# Server_CPU_IO.net
KiCad netlist of a schematic drawn in Altium Designer
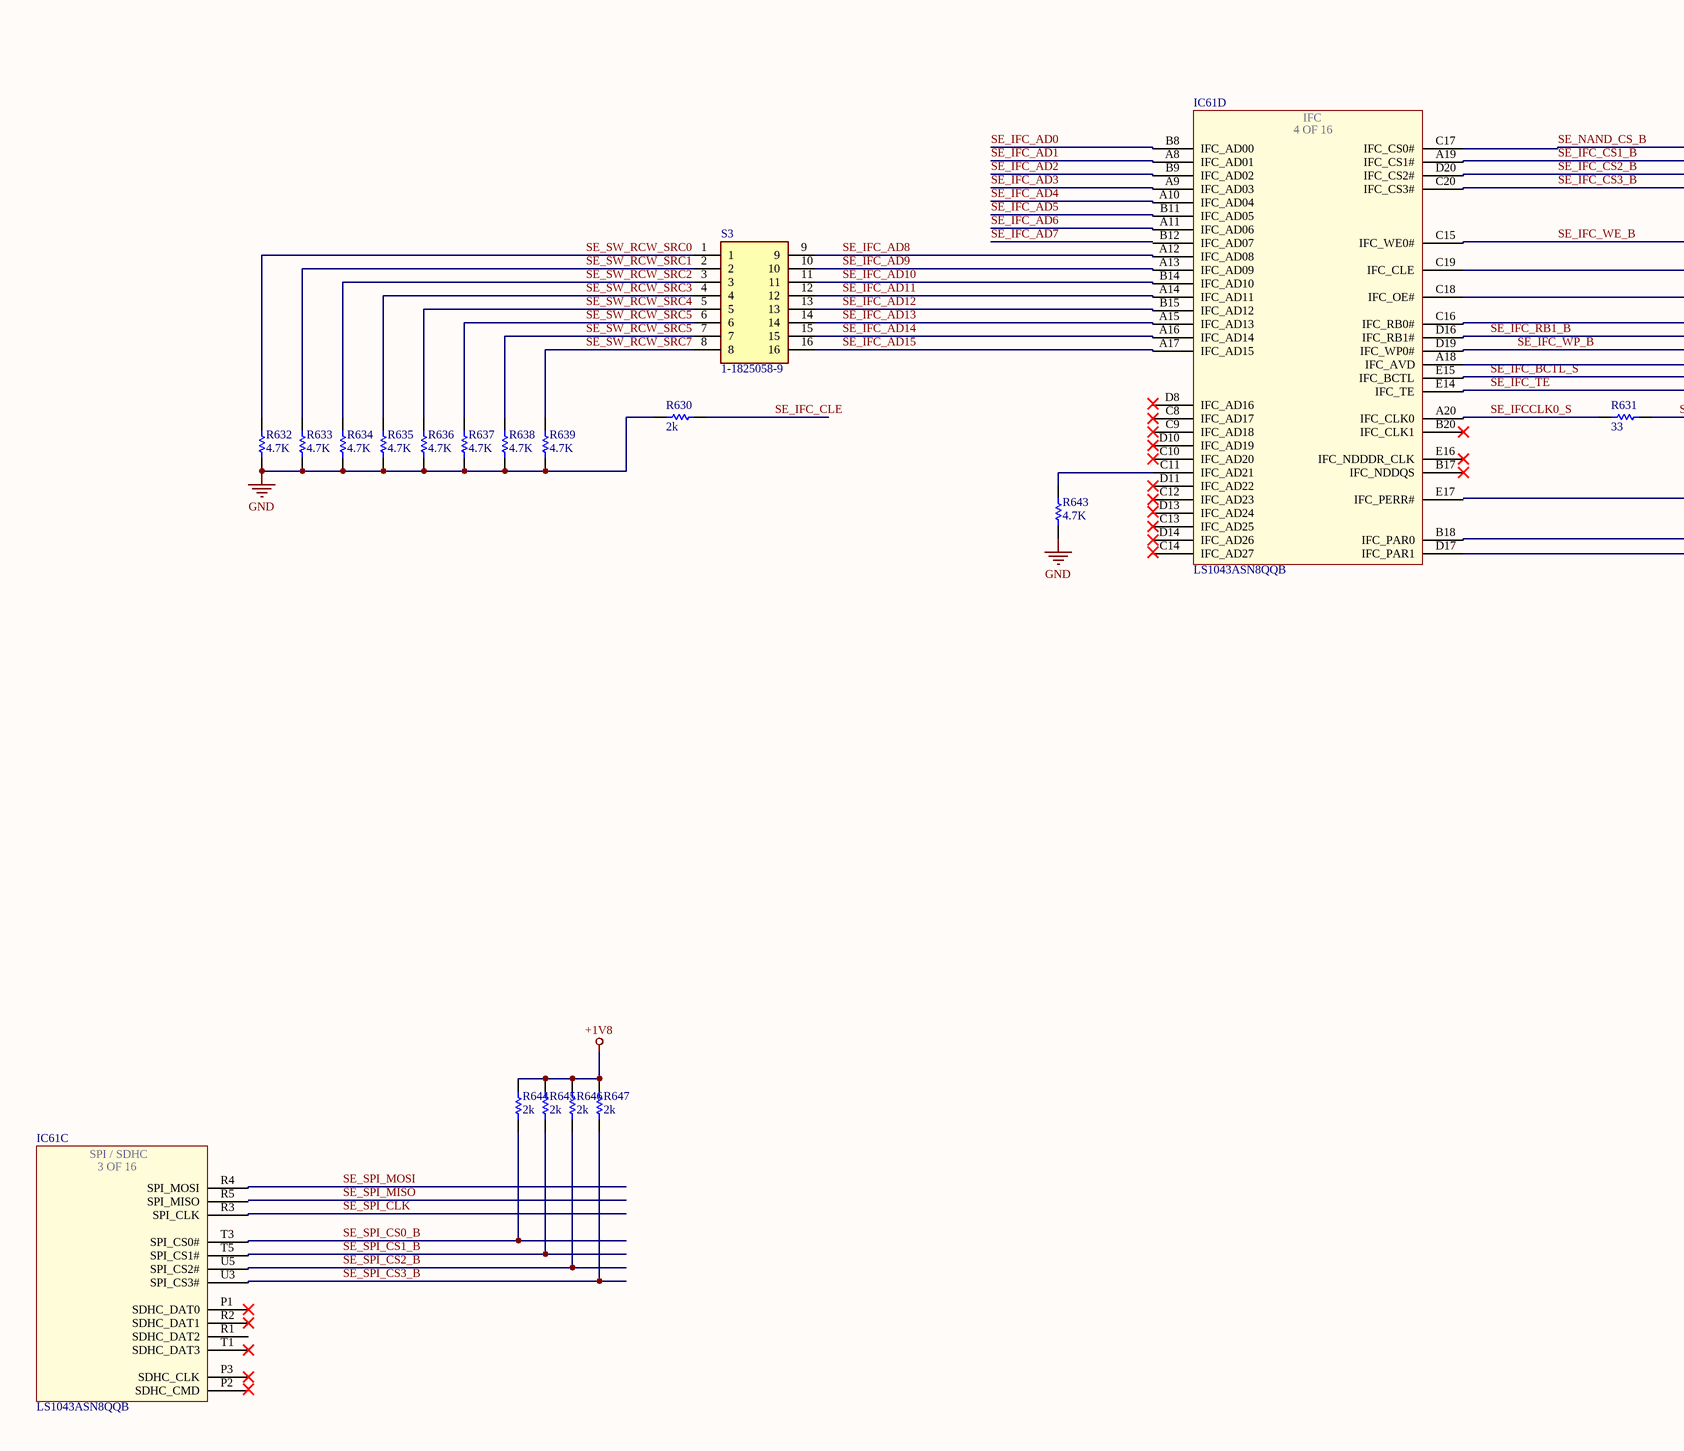
[diagram p0: Server_CPU_IO.SchDoc, left]
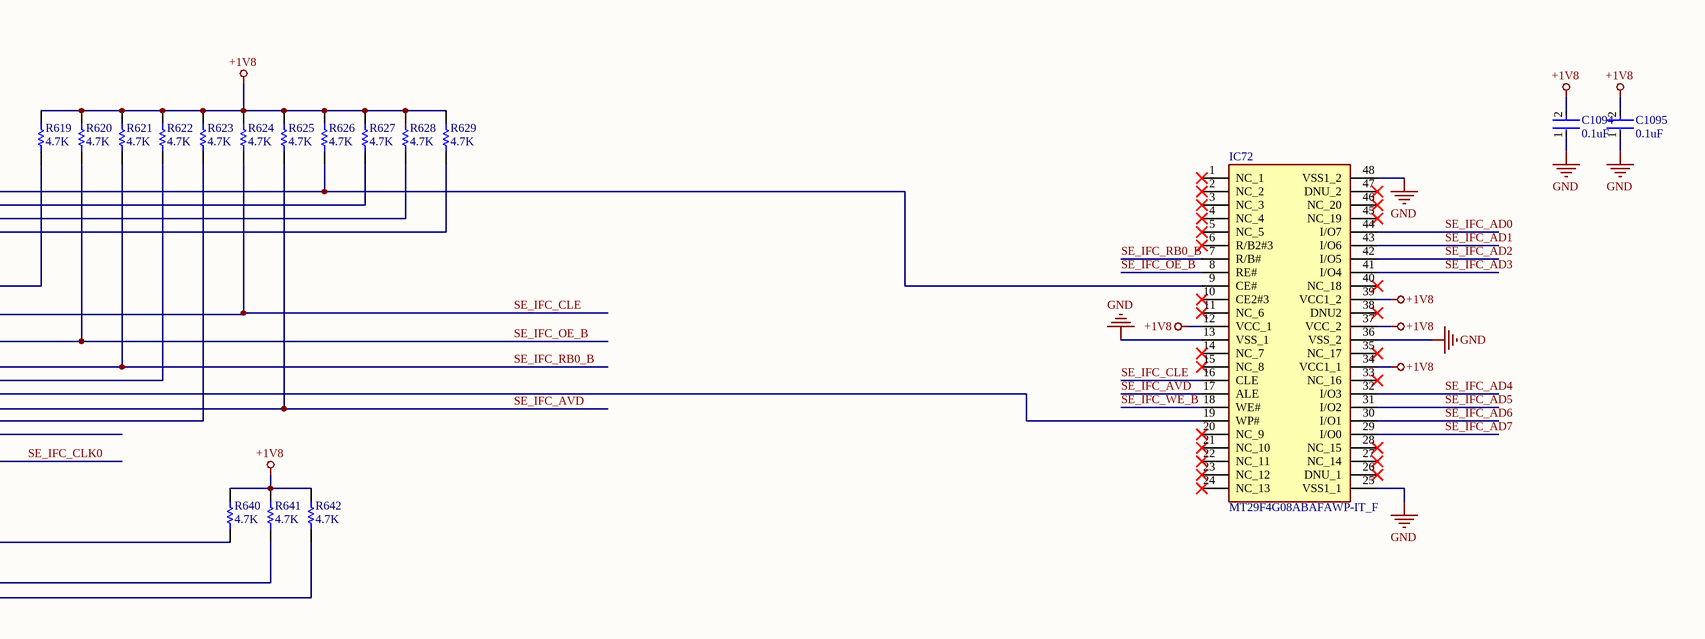
[diagram p1: Server_CPU_IO.SchDoc, right]

(export (version "E")
  (design (tool "Eeschema 10.0.6"))
  (components
    (comp (ref "C1094")
      (value "0.1uF")
      (footprint "FP-GRM15-MFG")
      (description "CAP CER 0.1UF 16V X7R 0402")
      (fields (field (name "MANUFACTURER PART NUMBER") "GRM155R71C104KA88D") (field (name "TOLERANCE") "10%"))
      (libsource (lib "Altium Content Vault") (part "236180d848d6139a670b325ea6854c9"))
    )
    (comp (ref "C1095")
      (value "0.1uF")
      (footprint "FP-GRM15-MFG")
      (description "CAP CER 0.1UF 16V X7R 0402")
      (fields (field (name "MANUFACTURER PART NUMBER") "GRM155R71C104KA88D") (field (name "TOLERANCE") "10%"))
      (libsource (lib "Altium Content Vault") (part "236180d848d6139a670b325ea6854c9"))
    )
    (comp (ref "IC61")
      (value "LS1043ASN8QQB")
      (footprint "SamacSys:BGA780C80P28X28_2300X2300X261")
      (description "Integrated Circuit")
      (fields (field (name "MOUSER PART NUMBER") "771-LS1043ASN8QQB"))
      (libsource (lib "SamacSys") (part "LS1043ASN8QQB"))
    )
    (comp (ref "IC72")
      (value "MT29F4G08ABAFAWP-IT_F")
      (footprint "SamacSys:SOP50P2000X120-48N")
      (description "Integrated Circuit")
      (fields
        (field (name "MANUFACTURER_PART_NUMBER") "MT29F4G08ABAFAWP-IT:F")
        (field (name "MOUSER PART NUMBER") "340-371016-TRAY")
      )
      (libsource (lib "*") (part "MT29F4G08ABAFAWP-IT_F"))
    )
    (comp (ref "R619")
      (value "4.7K")
      (footprint "RESC1005X40X25LL05T05")
      (description "Chip Resistor, 4.7 KOhm, +/- 1%, 0.1 W, -55 to 155 degC, 0402 (1005 Metric), RoHS, Tape and Reel")
      (fields (field (name "TOLERANCE") "1%") (field (name "PARTNUMBER") "ERJ-2RKF4701X"))
      (libsource (lib "Altium Content Vault") (part "RES-2"))
    )
    (comp (ref "R620")
      (value "4.7K")
      (footprint "RESC1005X40X25LL05T05")
      (description "Chip Resistor, 4.7 KOhm, +/- 1%, 0.1 W, -55 to 155 degC, 0402 (1005 Metric), RoHS, Tape and Reel")
      (fields (field (name "TOLERANCE") "1%") (field (name "PARTNUMBER") "ERJ-2RKF4701X"))
      (libsource (lib "Altium Content Vault") (part "RES-2"))
    )
    (comp (ref "R621")
      (value "4.7K")
      (footprint "RESC1005X40X25LL05T05")
      (description "Chip Resistor, 4.7 KOhm, +/- 1%, 0.1 W, -55 to 155 degC, 0402 (1005 Metric), RoHS, Tape and Reel")
      (fields (field (name "TOLERANCE") "1%") (field (name "PARTNUMBER") "ERJ-2RKF4701X"))
      (libsource (lib "Altium Content Vault") (part "RES-2"))
    )
    (comp (ref "R622")
      (value "4.7K")
      (footprint "RESC1005X40X25LL05T05")
      (description "Chip Resistor, 4.7 KOhm, +/- 1%, 0.1 W, -55 to 155 degC, 0402 (1005 Metric), RoHS, Tape and Reel")
      (fields (field (name "TOLERANCE") "1%") (field (name "PARTNUMBER") "ERJ-2RKF4701X"))
      (libsource (lib "Altium Content Vault") (part "RES-2"))
    )
    (comp (ref "R623")
      (value "4.7K")
      (footprint "RESC1005X40X25LL05T05")
      (description "Chip Resistor, 4.7 KOhm, +/- 1%, 0.1 W, -55 to 155 degC, 0402 (1005 Metric), RoHS, Tape and Reel")
      (fields (field (name "TOLERANCE") "1%") (field (name "PARTNUMBER") "ERJ-2RKF4701X"))
      (libsource (lib "Altium Content Vault") (part "RES-2"))
    )
    (comp (ref "R624")
      (value "4.7K")
      (footprint "RESC1005X40X25LL05T05")
      (description "Chip Resistor, 4.7 KOhm, +/- 1%, 0.1 W, -55 to 155 degC, 0402 (1005 Metric), RoHS, Tape and Reel")
      (fields (field (name "TOLERANCE") "1%") (field (name "PARTNUMBER") "ERJ-2RKF4701X"))
      (libsource (lib "Altium Content Vault") (part "RES-2"))
    )
    (comp (ref "R625")
      (value "4.7K")
      (footprint "RESC1005X40X25LL05T05")
      (description "Chip Resistor, 4.7 KOhm, +/- 1%, 0.1 W, -55 to 155 degC, 0402 (1005 Metric), RoHS, Tape and Reel")
      (fields (field (name "TOLERANCE") "1%") (field (name "PARTNUMBER") "ERJ-2RKF4701X"))
      (libsource (lib "Altium Content Vault") (part "RES-2"))
    )
    (comp (ref "R626")
      (value "4.7K")
      (footprint "RESC1005X40X25LL05T05")
      (description "Chip Resistor, 4.7 KOhm, +/- 1%, 0.1 W, -55 to 155 degC, 0402 (1005 Metric), RoHS, Tape and Reel")
      (fields (field (name "TOLERANCE") "1%") (field (name "PARTNUMBER") "ERJ-2RKF4701X"))
      (libsource (lib "Altium Content Vault") (part "RES-2"))
    )
    (comp (ref "R627")
      (value "4.7K")
      (footprint "RESC1005X40X25LL05T05")
      (description "Chip Resistor, 4.7 KOhm, +/- 1%, 0.1 W, -55 to 155 degC, 0402 (1005 Metric), RoHS, Tape and Reel")
      (fields (field (name "TOLERANCE") "1%") (field (name "PARTNUMBER") "ERJ-2RKF4701X"))
      (libsource (lib "Altium Content Vault") (part "RES-2"))
    )
    (comp (ref "R628")
      (value "4.7K")
      (footprint "RESC1005X40X25LL05T05")
      (description "Chip Resistor, 4.7 KOhm, +/- 1%, 0.1 W, -55 to 155 degC, 0402 (1005 Metric), RoHS, Tape and Reel")
      (fields (field (name "TOLERANCE") "1%") (field (name "PARTNUMBER") "ERJ-2RKF4701X"))
      (libsource (lib "Altium Content Vault") (part "RES-2"))
    )
    (comp (ref "R629")
      (value "4.7K")
      (footprint "RESC1005X40X25LL05T05")
      (description "Chip Resistor, 4.7 KOhm, +/- 1%, 0.1 W, -55 to 155 degC, 0402 (1005 Metric), RoHS, Tape and Reel")
      (fields (field (name "TOLERANCE") "1%") (field (name "PARTNUMBER") "ERJ-2RKF4701X"))
      (libsource (lib "Altium Content Vault") (part "RES-2"))
    )
    (comp (ref "R630")
      (value "2k")
      (footprint "RESC1005X40X25NL05T05")
      (description "Chip Resistor, 2 KOhm, +/- 1%, 100 mW, -55 to 155 degC, 0402 (1005 Metric), RoHS, Tape and Reel")
      (fields (field (name "MANUFACTURER") "Basic Passives") (field (name "TOLERANCE") "1%"))
      (libsource (lib "Altium Content Vault") (part "RES-2"))
    )
    (comp (ref "R631")
      (value "33")
      (footprint "RESC1005X40X25LL05T05")
      (fields (field (name "MANUFACTURER") "Panasonic") (field (name "PART NUMBER") "ERJ2RKF33R0X"))
      (libsource (lib "Altium Content Vault") (part "RES"))
    )
    (comp (ref "R632")
      (value "4.7K")
      (footprint "RESC1005X40X25LL05T05")
      (description "Chip Resistor, 4.7 KOhm, +/- 1%, 0.1 W, -55 to 155 degC, 0402 (1005 Metric), RoHS, Tape and Reel")
      (fields (field (name "TOLERANCE") "1%") (field (name "PARTNUMBER") "ERJ-2RKF4701X"))
      (libsource (lib "Altium Content Vault") (part "RES-2"))
    )
    (comp (ref "R633")
      (value "4.7K")
      (footprint "RESC1005X40X25LL05T05")
      (description "Chip Resistor, 4.7 KOhm, +/- 1%, 0.1 W, -55 to 155 degC, 0402 (1005 Metric), RoHS, Tape and Reel")
      (fields (field (name "TOLERANCE") "1%") (field (name "PARTNUMBER") "ERJ-2RKF4701X"))
      (libsource (lib "Altium Content Vault") (part "RES-2"))
    )
    (comp (ref "R634")
      (value "4.7K")
      (footprint "RESC1005X40X25LL05T05")
      (description "Chip Resistor, 4.7 KOhm, +/- 1%, 0.1 W, -55 to 155 degC, 0402 (1005 Metric), RoHS, Tape and Reel")
      (fields (field (name "TOLERANCE") "1%") (field (name "PARTNUMBER") "ERJ-2RKF4701X"))
      (libsource (lib "Altium Content Vault") (part "RES-2"))
    )
    (comp (ref "R635")
      (value "4.7K")
      (footprint "RESC1005X40X25LL05T05")
      (description "Chip Resistor, 4.7 KOhm, +/- 1%, 0.1 W, -55 to 155 degC, 0402 (1005 Metric), RoHS, Tape and Reel")
      (fields (field (name "TOLERANCE") "1%") (field (name "PARTNUMBER") "ERJ-2RKF4701X"))
      (libsource (lib "Altium Content Vault") (part "RES-2"))
    )
    (comp (ref "R636")
      (value "4.7K")
      (footprint "RESC1005X40X25LL05T05")
      (description "Chip Resistor, 4.7 KOhm, +/- 1%, 0.1 W, -55 to 155 degC, 0402 (1005 Metric), RoHS, Tape and Reel")
      (fields (field (name "TOLERANCE") "1%") (field (name "PARTNUMBER") "ERJ-2RKF4701X"))
      (libsource (lib "Altium Content Vault") (part "RES-2"))
    )
    (comp (ref "R637")
      (value "4.7K")
      (footprint "RESC1005X40X25LL05T05")
      (description "Chip Resistor, 4.7 KOhm, +/- 1%, 0.1 W, -55 to 155 degC, 0402 (1005 Metric), RoHS, Tape and Reel")
      (fields (field (name "TOLERANCE") "1%") (field (name "PARTNUMBER") "ERJ-2RKF4701X"))
      (libsource (lib "Altium Content Vault") (part "RES-2"))
    )
    (comp (ref "R638")
      (value "4.7K")
      (footprint "RESC1005X40X25LL05T05")
      (description "Chip Resistor, 4.7 KOhm, +/- 1%, 0.1 W, -55 to 155 degC, 0402 (1005 Metric), RoHS, Tape and Reel")
      (fields (field (name "TOLERANCE") "1%") (field (name "PARTNUMBER") "ERJ-2RKF4701X"))
      (libsource (lib "Altium Content Vault") (part "RES-2"))
    )
    (comp (ref "R639")
      (value "4.7K")
      (footprint "RESC1005X40X25LL05T05")
      (description "Chip Resistor, 4.7 KOhm, +/- 1%, 0.1 W, -55 to 155 degC, 0402 (1005 Metric), RoHS, Tape and Reel")
      (fields (field (name "TOLERANCE") "1%") (field (name "PARTNUMBER") "ERJ-2RKF4701X"))
      (libsource (lib "Altium Content Vault") (part "RES-2"))
    )
    (comp (ref "R640")
      (value "4.7K")
      (footprint "RESC1005X40X25LL05T05")
      (description "Chip Resistor, 4.7 KOhm, +/- 1%, 0.1 W, -55 to 155 degC, 0402 (1005 Metric), RoHS, Tape and Reel")
      (fields (field (name "TOLERANCE") "1%") (field (name "PARTNUMBER") "ERJ-2RKF4701X"))
      (libsource (lib "Altium Content Vault") (part "RES-2"))
    )
    (comp (ref "R641")
      (value "4.7K")
      (footprint "RESC1005X40X25LL05T05")
      (description "Chip Resistor, 4.7 KOhm, +/- 1%, 0.1 W, -55 to 155 degC, 0402 (1005 Metric), RoHS, Tape and Reel")
      (fields (field (name "TOLERANCE") "1%") (field (name "PARTNUMBER") "ERJ-2RKF4701X"))
      (libsource (lib "Altium Content Vault") (part "RES-2"))
    )
    (comp (ref "R642")
      (value "4.7K")
      (footprint "RESC1005X40X25LL05T05")
      (description "Chip Resistor, 4.7 KOhm, +/- 1%, 0.1 W, -55 to 155 degC, 0402 (1005 Metric), RoHS, Tape and Reel")
      (fields (field (name "TOLERANCE") "1%") (field (name "PARTNUMBER") "ERJ-2RKF4701X"))
      (libsource (lib "Altium Content Vault") (part "RES-2"))
    )
    (comp (ref "R643")
      (value "4.7K")
      (footprint "RESC1005X40X25LL05T05")
      (description "Chip Resistor, 4.7 KOhm, +/- 1%, 0.1 W, -55 to 155 degC, 0402 (1005 Metric), RoHS, Tape and Reel")
      (fields (field (name "TOLERANCE") "1%") (field (name "PARTNUMBER") "ERJ-2RKF4701X"))
      (libsource (lib "Altium Content Vault") (part "RES-2"))
    )
    (comp (ref "R644")
      (value "2k")
      (footprint "RESC1005X40X25NL05T05")
      (description "Chip Resistor, 2 KOhm, +/- 1%, 100 mW, -55 to 155 degC, 0402 (1005 Metric), RoHS, Tape and Reel")
      (fields (field (name "MANUFACTURER") "Basic Passives") (field (name "TOLERANCE") "1%"))
      (libsource (lib "Altium Content Vault") (part "RES-2"))
    )
    (comp (ref "R645")
      (value "2k")
      (footprint "RESC1005X40X25NL05T05")
      (description "Chip Resistor, 2 KOhm, +/- 1%, 100 mW, -55 to 155 degC, 0402 (1005 Metric), RoHS, Tape and Reel")
      (fields (field (name "MANUFACTURER") "Basic Passives") (field (name "TOLERANCE") "1%"))
      (libsource (lib "Altium Content Vault") (part "RES-2"))
    )
    (comp (ref "R646")
      (value "2k")
      (footprint "RESC1005X40X25NL05T05")
      (description "Chip Resistor, 2 KOhm, +/- 1%, 100 mW, -55 to 155 degC, 0402 (1005 Metric), RoHS, Tape and Reel")
      (fields (field (name "MANUFACTURER") "Basic Passives") (field (name "TOLERANCE") "1%"))
      (libsource (lib "Altium Content Vault") (part "RES-2"))
    )
    (comp (ref "R647")
      (value "2k")
      (footprint "RESC1005X40X25NL05T05")
      (description "Chip Resistor, 2 KOhm, +/- 1%, 100 mW, -55 to 155 degC, 0402 (1005 Metric), RoHS, Tape and Reel")
      (fields (field (name "MANUFACTURER") "Basic Passives") (field (name "TOLERANCE") "1%"))
      (libsource (lib "Altium Content Vault") (part "RES-2"))
    )
    (comp (ref "S3")
      (value "1-1825058-9")
      (footprint "SamacSys:118250589")
      (description "Switch")
      (libsource (lib "*") (part "1-1825058-9"))
    )
  )
  (nets
    (net (code "1") (name "+1V8") (class "Default")
      (node (ref "C1094") (pin "2") (pinfunction "2_2") (pintype "passive"))
      (node (ref "C1095") (pin "2") (pinfunction "2_2") (pintype "passive"))
      (node (ref "IC72") (pin "12") (pinfunction "VCC_1_12") (pintype "passive"))
      (node (ref "IC72") (pin "34") (pinfunction "VCC1_1_34") (pintype "passive"))
      (node (ref "IC72") (pin "37") (pinfunction "VCC_2_37") (pintype "passive"))
      (node (ref "IC72") (pin "39") (pinfunction "VCC1_2_39") (pintype "passive"))
      (node (ref "R619") (pin "2") (pinfunction "2_2") (pintype "passive"))
      (node (ref "R620") (pin "2") (pinfunction "2_2") (pintype "passive"))
      (node (ref "R621") (pin "2") (pinfunction "2_2") (pintype "passive"))
      (node (ref "R622") (pin "2") (pinfunction "2_2") (pintype "passive"))
      (node (ref "R623") (pin "2") (pinfunction "2_2") (pintype "passive"))
      (node (ref "R624") (pin "2") (pinfunction "2_2") (pintype "passive"))
      (node (ref "R625") (pin "2") (pinfunction "2_2") (pintype "passive"))
      (node (ref "R626") (pin "2") (pinfunction "2_2") (pintype "passive"))
      (node (ref "R627") (pin "2") (pinfunction "2_2") (pintype "passive"))
      (node (ref "R628") (pin "2") (pinfunction "2_2") (pintype "passive"))
      (node (ref "R629") (pin "2") (pinfunction "2_2") (pintype "passive"))
      (node (ref "R640") (pin "2") (pinfunction "2_2") (pintype "passive"))
      (node (ref "R641") (pin "2") (pinfunction "2_2") (pintype "passive"))
      (node (ref "R642") (pin "2") (pinfunction "2_2") (pintype "passive"))
      (node (ref "R644") (pin "1") (pinfunction "1_1") (pintype "passive"))
      (node (ref "R645") (pin "1") (pinfunction "1_1") (pintype "passive"))
      (node (ref "R646") (pin "1") (pinfunction "1_1") (pintype "passive"))
      (node (ref "R647") (pin "1") (pinfunction "1_1") (pintype "passive"))
    )
    (net (code "2") (name "/SE_IFCCLK0_S") (class "Default")
      (node (ref "IC61") (pin "A20") (pinfunction "IFC_CLK0_A20") (pintype "passive"))
      (node (ref "R631") (pin "1") (pinfunction "1_1") (pintype "passive"))
    )
    (net (code "3") (name "/SE_IFC_AD0") (class "Default")
      (node (ref "IC61") (pin "B8") (pinfunction "IFC_AD00_B8") (pintype "passive"))
      (node (ref "IC72") (pin "44") (pinfunction "I/O7_44") (pintype "passive"))
    )
    (net (code "4") (name "/SE_IFC_AD1") (class "Default")
      (node (ref "IC61") (pin "A8") (pinfunction "IFC_AD01_A8") (pintype "passive"))
      (node (ref "IC72") (pin "43") (pinfunction "I/O6_43") (pintype "passive"))
    )
    (net (code "5") (name "/SE_IFC_AD2") (class "Default")
      (node (ref "IC61") (pin "B9") (pinfunction "IFC_AD02_B9") (pintype "passive"))
      (node (ref "IC72") (pin "42") (pinfunction "I/O5_42") (pintype "passive"))
    )
    (net (code "6") (name "/SE_IFC_AD3") (class "Default")
      (node (ref "IC61") (pin "A9") (pinfunction "IFC_AD03_A9") (pintype "passive"))
      (node (ref "IC72") (pin "41") (pinfunction "I/O4_41") (pintype "passive"))
    )
    (net (code "7") (name "/SE_IFC_AD4") (class "Default")
      (node (ref "IC61") (pin "A10") (pinfunction "IFC_AD04_A10") (pintype "passive"))
      (node (ref "IC72") (pin "32") (pinfunction "I/O3_32") (pintype "passive"))
    )
    (net (code "8") (name "/SE_IFC_AD5") (class "Default")
      (node (ref "IC61") (pin "B11") (pinfunction "IFC_AD05_B11") (pintype "passive"))
      (node (ref "IC72") (pin "31") (pinfunction "I/O2_31") (pintype "passive"))
    )
    (net (code "9") (name "/SE_IFC_AD6") (class "Default")
      (node (ref "IC61") (pin "A11") (pinfunction "IFC_AD06_A11") (pintype "passive"))
      (node (ref "IC72") (pin "30") (pinfunction "I/O1_30") (pintype "passive"))
    )
    (net (code "10") (name "/SE_IFC_AD7") (class "Default")
      (node (ref "IC72") (pin "29") (pinfunction "I/O0_29") (pintype "passive"))
    )
    (net (code "11") (name "/SE_IFC_AD8") (class "Default")
      (node (ref "IC61") (pin "A12") (pinfunction "IFC_AD08_A12") (pintype "passive"))
      (node (ref "S3") (pin "9") (pinfunction "9_9") (pintype "passive"))
    )
    (net (code "12") (name "/SE_IFC_AD9") (class "Default")
      (node (ref "IC61") (pin "A13") (pinfunction "IFC_AD09_A13") (pintype "passive"))
      (node (ref "S3") (pin "10") (pinfunction "10_10") (pintype "passive"))
    )
    (net (code "13") (name "/SE_IFC_AD10") (class "Default")
      (node (ref "IC61") (pin "B14") (pinfunction "IFC_AD10_B14") (pintype "passive"))
      (node (ref "S3") (pin "11") (pinfunction "11_11") (pintype "passive"))
    )
    (net (code "14") (name "/SE_IFC_AD11") (class "Default")
      (node (ref "IC61") (pin "A14") (pinfunction "IFC_AD11_A14") (pintype "passive"))
      (node (ref "S3") (pin "12") (pinfunction "12_12") (pintype "passive"))
    )
    (net (code "15") (name "/SE_IFC_AD12") (class "Default")
      (node (ref "IC61") (pin "B15") (pinfunction "IFC_AD12_B15") (pintype "passive"))
      (node (ref "S3") (pin "13") (pinfunction "13_13") (pintype "passive"))
    )
    (net (code "16") (name "/SE_IFC_AD13") (class "Default")
      (node (ref "IC61") (pin "A15") (pinfunction "IFC_AD13_A15") (pintype "passive"))
      (node (ref "S3") (pin "14") (pinfunction "14_14") (pintype "passive"))
    )
    (net (code "17") (name "/SE_IFC_AD14") (class "Default")
      (node (ref "IC61") (pin "A16") (pinfunction "IFC_AD14_A16") (pintype "passive"))
      (node (ref "S3") (pin "15") (pinfunction "15_15") (pintype "passive"))
    )
    (net (code "18") (name "/SE_IFC_AD15") (class "Default")
      (node (ref "IC61") (pin "A17") (pinfunction "IFC_AD15_A17") (pintype "passive"))
      (node (ref "S3") (pin "16") (pinfunction "16_16") (pintype "passive"))
    )
    (net (code "19") (name "/SE_IFC_AVD") (class "Default")
      (node (ref "IC61") (pin "A18") (pinfunction "IFC_AVD_A18") (pintype "passive"))
      (node (ref "IC72") (pin "17") (pinfunction "ALE_17") (pintype "passive"))
      (node (ref "R625") (pin "1") (pinfunction "1_1") (pintype "passive"))
    )
    (net (code "20") (name "/SE_IFC_BCTL_S") (class "Default")
      (node (ref "IC61") (pin "E15") (pinfunction "IFC_BCTL_E15") (pintype "passive"))
      (node (ref "R623") (pin "1") (pinfunction "1_1") (pintype "passive"))
    )
    (net (code "21") (name "/SE_IFC_CLE") (class "Default")
      (node (ref "IC61") (pin "C19") (pinfunction "IFC_CLE_C19") (pintype "passive"))
      (node (ref "IC72") (pin "16") (pinfunction "CLE_16") (pintype "passive"))
      (node (ref "R624") (pin "1") (pinfunction "1_1") (pintype "passive"))
      (node (ref "R630") (pin "1") (pinfunction "1_1") (pintype "passive"))
    )
    (net (code "22") (name "/SE_IFC_CLK0") (class "Default")
      (node (ref "R631") (pin "2") (pinfunction "2_2") (pintype "passive"))
    )
    (net (code "23") (name "/SE_IFC_CS1_B") (class "Default")
      (node (ref "IC61") (pin "A19") (pinfunction "IFC_CS1#_A19") (pintype "passive"))
      (node (ref "R627") (pin "1") (pinfunction "1_1") (pintype "passive"))
    )
    (net (code "24") (name "/SE_IFC_CS2_B") (class "Default")
      (node (ref "IC61") (pin "D20") (pinfunction "IFC_CS2#_D20") (pintype "passive"))
      (node (ref "R628") (pin "1") (pinfunction "1_1") (pintype "passive"))
    )
    (net (code "25") (name "/SE_IFC_CS3_B") (class "Default")
      (node (ref "IC61") (pin "C20") (pinfunction "IFC_CS3#_C20") (pintype "passive"))
      (node (ref "R629") (pin "1") (pinfunction "1_1") (pintype "passive"))
    )
    (net (code "26") (name "/SE_IFC_OE_B") (class "Default")
      (node (ref "IC61") (pin "C18") (pinfunction "IFC_OE#_C18") (pintype "passive"))
      (node (ref "IC72") (pin "8") (pinfunction "RE#_8") (pintype "passive"))
      (node (ref "R620") (pin "1") (pinfunction "1_1") (pintype "passive"))
    )
    (net (code "27") (name "/SE_IFC_RB0_B") (class "Default")
      (node (ref "IC61") (pin "C16") (pinfunction "IFC_RB0#_C16") (pintype "passive"))
      (node (ref "IC72") (pin "7") (pinfunction "R/B#_7") (pintype "passive"))
      (node (ref "R621") (pin "1") (pinfunction "1_1") (pintype "passive"))
    )
    (net (code "28") (name "/SE_IFC_RB1_B") (class "Default")
      (node (ref "IC61") (pin "D16") (pinfunction "IFC_RB1#_D16") (pintype "passive"))
      (node (ref "R622") (pin "1") (pinfunction "1_1") (pintype "passive"))
    )
    (net (code "29") (name "/SE_IFC_TE") (class "Default")
      (node (ref "IC61") (pin "E14") (pinfunction "IFC_TE_E14") (pintype "passive"))
    )
    (net (code "30") (name "/SE_IFC_WE_B") (class "Default")
      (node (ref "IC61") (pin "C15") (pinfunction "IFC_WE0#_C15") (pintype "passive"))
      (node (ref "IC72") (pin "18") (pinfunction "WE#_18") (pintype "passive"))
      (node (ref "R619") (pin "1") (pinfunction "1_1") (pintype "passive"))
    )
    (net (code "31") (name "/SE_IFC_WP_B") (class "Default")
      (node (ref "IC61") (pin "D19") (pinfunction "IFC_WP0#_D19") (pintype "passive"))
      (node (ref "IC72") (pin "19") (pinfunction "WP#_19") (pintype "passive"))
    )
    (net (code "32") (name "/SE_NAND_CS_B") (class "Default")
      (node (ref "IC61") (pin "C17") (pinfunction "IFC_CS0#_C17") (pintype "passive"))
      (node (ref "IC72") (pin "9") (pinfunction "CE#_9") (pintype "passive"))
      (node (ref "R626") (pin "1") (pinfunction "1_1") (pintype "passive"))
    )
    (net (code "33") (name "/SE_SPI_CLK") (class "Default")
      (node (ref "IC61") (pin "R3") (pinfunction "SPI_CLK_R3") (pintype "passive"))
    )
    (net (code "34") (name "/SE_SPI_CS0_B") (class "Default")
      (node (ref "IC61") (pin "T3") (pinfunction "SPI_CS0#_T3") (pintype "passive"))
      (node (ref "R644") (pin "2") (pinfunction "2_2") (pintype "passive"))
    )
    (net (code "35") (name "/SE_SPI_CS1_B") (class "Default")
      (node (ref "IC61") (pin "T5") (pinfunction "SPI_CS1#_T5") (pintype "passive"))
      (node (ref "R645") (pin "2") (pinfunction "2_2") (pintype "passive"))
    )
    (net (code "36") (name "/SE_SPI_CS2_B") (class "Default")
      (node (ref "IC61") (pin "U5") (pinfunction "SPI_CS2#_U5") (pintype "passive"))
      (node (ref "R646") (pin "2") (pinfunction "2_2") (pintype "passive"))
    )
    (net (code "37") (name "/SE_SPI_CS3_B") (class "Default")
      (node (ref "IC61") (pin "U3") (pinfunction "SPI_CS3#_U3") (pintype "passive"))
      (node (ref "R647") (pin "2") (pinfunction "2_2") (pintype "passive"))
    )
    (net (code "39") (name "/SE_SPI_MOSI") (class "Default")
      (node (ref "IC61") (pin "R4") (pinfunction "SPI_MOSI_R4") (pintype "passive"))
    )
    (net (code "40") (name "/SE_SW_RCW_SRC0") (class "Default")
      (node (ref "R632") (pin "2") (pinfunction "2_2") (pintype "passive"))
      (node (ref "S3") (pin "1") (pinfunction "1_1") (pintype "passive"))
    )
    (net (code "41") (name "/SE_SW_RCW_SRC1") (class "Default")
      (node (ref "R633") (pin "2") (pinfunction "2_2") (pintype "passive"))
      (node (ref "S3") (pin "2") (pinfunction "2_2") (pintype "passive"))
    )
    (net (code "42") (name "/SE_SW_RCW_SRC2") (class "Default")
      (node (ref "R634") (pin "2") (pinfunction "2_2") (pintype "passive"))
      (node (ref "S3") (pin "3") (pinfunction "3_3") (pintype "passive"))
    )
    (net (code "43") (name "/SE_SW_RCW_SRC3") (class "Default")
      (node (ref "R635") (pin "2") (pinfunction "2_2") (pintype "passive"))
      (node (ref "S3") (pin "4") (pinfunction "4_4") (pintype "passive"))
    )
    (net (code "44") (name "/SE_SW_RCW_SRC4") (class "Default")
      (node (ref "R636") (pin "2") (pinfunction "2_2") (pintype "passive"))
      (node (ref "S3") (pin "5") (pinfunction "5_5") (pintype "passive"))
    )
    (net (code "45") (name "/SE_SW_RCW_SRC5") (class "Default")
      (node (ref "R637") (pin "2") (pinfunction "2_2") (pintype "passive"))
      (node (ref "R638") (pin "2") (pinfunction "2_2") (pintype "passive"))
      (node (ref "S3") (pin "6") (pinfunction "6_6") (pintype "passive"))
      (node (ref "S3") (pin "7") (pinfunction "7_7") (pintype "passive"))
    )
    (net (code "46") (name "/SE_SW_RCW_SRC7") (class "Default")
      (node (ref "R639") (pin "2") (pinfunction "2_2") (pintype "passive"))
      (node (ref "S3") (pin "8") (pinfunction "8_8") (pintype "passive"))
    )
    (net (code "47") (name "GND") (class "Default")
      (node (ref "C1094") (pin "1") (pinfunction "1_1") (pintype "passive"))
      (node (ref "C1095") (pin "1") (pinfunction "1_1") (pintype "passive"))
      (node (ref "IC72") (pin "13") (pinfunction "VSS_1_13") (pintype "passive"))
      (node (ref "IC72") (pin "25") (pinfunction "VSS1_1_25") (pintype "passive"))
      (node (ref "IC72") (pin "36") (pinfunction "VSS_2_36") (pintype "passive"))
      (node (ref "IC72") (pin "48") (pinfunction "VSS1_2_48") (pintype "passive"))
      (node (ref "R630") (pin "2") (pinfunction "2_2") (pintype "passive"))
      (node (ref "R632") (pin "1") (pinfunction "1_1") (pintype "passive"))
      (node (ref "R633") (pin "1") (pinfunction "1_1") (pintype "passive"))
      (node (ref "R634") (pin "1") (pinfunction "1_1") (pintype "passive"))
      (node (ref "R635") (pin "1") (pinfunction "1_1") (pintype "passive"))
      (node (ref "R636") (pin "1") (pinfunction "1_1") (pintype "passive"))
      (node (ref "R637") (pin "1") (pinfunction "1_1") (pintype "passive"))
      (node (ref "R638") (pin "1") (pinfunction "1_1") (pintype "passive"))
      (node (ref "R639") (pin "1") (pinfunction "1_1") (pintype "passive"))
      (node (ref "R643") (pin "1") (pinfunction "1_1") (pintype "passive"))
    )
    (net (code "48") (name "Net-(IC61D-IFC_AD21)") (class "Default")
      (node (ref "IC61") (pin "C11") (pinfunction "IFC_AD21_C11") (pintype "passive"))
      (node (ref "R643") (pin "2") (pinfunction "2_2") (pintype "passive"))
    )
    (net (code "49") (name "Net-(IC61D-IFC_PAR0)") (class "Default")
      (node (ref "IC61") (pin "B18") (pinfunction "IFC_PAR0_B18") (pintype "passive"))
      (node (ref "R641") (pin "1") (pinfunction "1_1") (pintype "passive"))
    )
    (net (code "50") (name "Net-(IC61D-IFC_PAR1)") (class "Default")
      (node (ref "IC61") (pin "D17") (pinfunction "IFC_PAR1_D17") (pintype "passive"))
      (node (ref "R642") (pin "1") (pinfunction "1_1") (pintype "passive"))
    )
    (net (code "51") (name "unconnected-(IC61C-SDHC_CLK-PadP3)") (class "Default")
      (node (ref "IC61") (pin "P3") (pinfunction "SDHC_CLK_P3") (pintype "passive+no_connect"))
    )
    (net (code "52") (name "unconnected-(IC61C-SDHC_CMD-PadP2)") (class "Default")
      (node (ref "IC61") (pin "P2") (pinfunction "SDHC_CMD_P2") (pintype "passive"))
    )
    (net (code "53") (name "unconnected-(IC61C-SDHC_DAT0-PadP1)") (class "Default")
      (node (ref "IC61") (pin "P1") (pinfunction "SDHC_DAT0_P1") (pintype "passive+no_connect"))
    )
    (net (code "54") (name "unconnected-(IC61C-SDHC_DAT1-PadR2)") (class "Default")
      (node (ref "IC61") (pin "R2") (pinfunction "SDHC_DAT1_R2") (pintype "passive+no_connect"))
    )
    (net (code "55") (name "unconnected-(IC61C-SDHC_DAT2-PadR1)") (class "Default")
      (node (ref "IC61") (pin "R1") (pinfunction "SDHC_DAT2_R1") (pintype "passive"))
    )
    (net (code "56") (name "unconnected-(IC61C-SDHC_DAT3-PadT1)") (class "Default")
      (node (ref "IC61") (pin "T1") (pinfunction "SDHC_DAT3_T1") (pintype "passive+no_connect"))
    )
    (net (code "57") (name "unconnected-(IC61C-SPI_MISO-PadR5)") (class "Default")
      (node (ref "IC61") (pin "R5") (pinfunction "SPI_MISO_R5") (pintype "passive"))
    )
    (net (code "58") (name "unconnected-(IC61D-IFC_AD07-PadB12)") (class "Default")
      (node (ref "IC61") (pin "B12") (pinfunction "IFC_AD07_B12") (pintype "passive"))
    )
    (net (code "59") (name "unconnected-(IC61D-IFC_AD16-PadD8)") (class "Default")
      (node (ref "IC61") (pin "D8") (pinfunction "IFC_AD16_D8") (pintype "passive"))
    )
    (net (code "60") (name "unconnected-(IC61D-IFC_AD17-PadC8)") (class "Default")
      (node (ref "IC61") (pin "C8") (pinfunction "IFC_AD17_C8") (pintype "passive+no_connect"))
    )
    (net (code "61") (name "unconnected-(IC61D-IFC_AD18-PadC9)") (class "Default")
      (node (ref "IC61") (pin "C9") (pinfunction "IFC_AD18_C9") (pintype "passive+no_connect"))
    )
    (net (code "62") (name "unconnected-(IC61D-IFC_AD19-PadD10)") (class "Default")
      (node (ref "IC61") (pin "D10") (pinfunction "IFC_AD19_D10") (pintype "passive+no_connect"))
    )
    (net (code "63") (name "unconnected-(IC61D-IFC_AD20-PadC10)") (class "Default")
      (node (ref "IC61") (pin "C10") (pinfunction "IFC_AD20_C10") (pintype "passive+no_connect"))
    )
    (net (code "64") (name "unconnected-(IC61D-IFC_AD22-PadD11)") (class "Default")
      (node (ref "IC61") (pin "D11") (pinfunction "IFC_AD22_D11") (pintype "passive+no_connect"))
    )
    (net (code "65") (name "unconnected-(IC61D-IFC_AD23-PadC12)") (class "Default")
      (node (ref "IC61") (pin "C12") (pinfunction "IFC_AD23_C12") (pintype "passive+no_connect"))
    )
    (net (code "66") (name "unconnected-(IC61D-IFC_AD24-PadD13)") (class "Default")
      (node (ref "IC61") (pin "D13") (pinfunction "IFC_AD24_D13") (pintype "passive"))
    )
    (net (code "67") (name "unconnected-(IC61D-IFC_AD25-PadC13)") (class "Default")
      (node (ref "IC61") (pin "C13") (pinfunction "IFC_AD25_C13") (pintype "passive+no_connect"))
    )
    (net (code "68") (name "unconnected-(IC61D-IFC_AD26-PadD14)") (class "Default")
      (node (ref "IC61") (pin "D14") (pinfunction "IFC_AD26_D14") (pintype "passive+no_connect"))
    )
    (net (code "69") (name "unconnected-(IC61D-IFC_AD27-PadC14)") (class "Default")
      (node (ref "IC61") (pin "C14") (pinfunction "IFC_AD27_C14") (pintype "passive"))
    )
    (net (code "70") (name "unconnected-(IC61D-IFC_CLK1-PadB20)") (class "Default")
      (node (ref "IC61") (pin "B20") (pinfunction "IFC_CLK1_B20") (pintype "passive+no_connect"))
    )
    (net (code "71") (name "unconnected-(IC61D-IFC_NDDDR_CLK-PadE16)") (class "Default")
      (node (ref "IC61") (pin "E16") (pinfunction "IFC_NDDDR_CLK_E16") (pintype "passive+no_connect"))
    )
    (net (code "72") (name "unconnected-(IC61D-IFC_NDDQS-PadB17)") (class "Default")
      (node (ref "IC61") (pin "B17") (pinfunction "IFC_NDDQS_B17") (pintype "passive+no_connect"))
    )
    (net (code "73") (name "unconnected-(IC61D-IFC_PERR#-PadE17)") (class "Default")
      (node (ref "IC61") (pin "E17") (pinfunction "IFC_PERR#_E17") (pintype "passive"))
    )
    (net (code "74") (name "unconnected-(IC72-CE2#3-Pad10)") (class "Default")
      (node (ref "IC72") (pin "10") (pinfunction "CE2#3_10") (pintype "passive+no_connect"))
    )
    (net (code "75") (name "unconnected-(IC72-DNU2-Pad38)") (class "Default")
      (node (ref "IC72") (pin "38") (pinfunction "DNU2_38") (pintype "passive+no_connect"))
    )
    (net (code "76") (name "unconnected-(IC72-DNU_1-Pad26)") (class "Default")
      (node (ref "IC72") (pin "26") (pinfunction "DNU_1_26") (pintype "passive+no_connect"))
    )
    (net (code "77") (name "unconnected-(IC72-DNU_2-Pad47)") (class "Default")
      (node (ref "IC72") (pin "47") (pinfunction "DNU_2_47") (pintype "passive+no_connect"))
    )
    (net (code "78") (name "unconnected-(IC72-NC_1-Pad1)") (class "Default")
      (node (ref "IC72") (pin "1") (pinfunction "NC_1_1") (pintype "passive+no_connect"))
    )
    (net (code "79") (name "unconnected-(IC72-NC_2-Pad2)") (class "Default")
      (node (ref "IC72") (pin "2") (pinfunction "NC_2_2") (pintype "passive+no_connect"))
    )
    (net (code "80") (name "unconnected-(IC72-NC_3-Pad3)") (class "Default")
      (node (ref "IC72") (pin "3") (pinfunction "NC_3_3") (pintype "passive+no_connect"))
    )
    (net (code "81") (name "unconnected-(IC72-NC_4-Pad4)") (class "Default")
      (node (ref "IC72") (pin "4") (pinfunction "NC_4_4") (pintype "passive+no_connect"))
    )
    (net (code "82") (name "unconnected-(IC72-NC_5-Pad5)") (class "Default")
      (node (ref "IC72") (pin "5") (pinfunction "NC_5_5") (pintype "passive+no_connect"))
    )
    (net (code "83") (name "unconnected-(IC72-NC_6-Pad11)") (class "Default")
      (node (ref "IC72") (pin "11") (pinfunction "NC_6_11") (pintype "passive+no_connect"))
    )
    (net (code "84") (name "unconnected-(IC72-NC_7-Pad14)") (class "Default")
      (node (ref "IC72") (pin "14") (pinfunction "NC_7_14") (pintype "passive+no_connect"))
    )
    (net (code "85") (name "unconnected-(IC72-NC_8-Pad15)") (class "Default")
      (node (ref "IC72") (pin "15") (pinfunction "NC_8_15") (pintype "passive+no_connect"))
    )
    (net (code "86") (name "unconnected-(IC72-NC_9-Pad20)") (class "Default")
      (node (ref "IC72") (pin "20") (pinfunction "NC_9_20") (pintype "passive+no_connect"))
    )
    (net (code "87") (name "unconnected-(IC72-NC_10-Pad21)") (class "Default")
      (node (ref "IC72") (pin "21") (pinfunction "NC_10_21") (pintype "passive+no_connect"))
    )
    (net (code "88") (name "unconnected-(IC72-NC_11-Pad22)") (class "Default")
      (node (ref "IC72") (pin "22") (pinfunction "NC_11_22") (pintype "passive+no_connect"))
    )
    (net (code "89") (name "unconnected-(IC72-NC_12-Pad23)") (class "Default")
      (node (ref "IC72") (pin "23") (pinfunction "NC_12_23") (pintype "passive+no_connect"))
    )
    (net (code "90") (name "unconnected-(IC72-NC_13-Pad24)") (class "Default")
      (node (ref "IC72") (pin "24") (pinfunction "NC_13_24") (pintype "passive+no_connect"))
    )
    (net (code "91") (name "unconnected-(IC72-NC_14-Pad27)") (class "Default")
      (node (ref "IC72") (pin "27") (pinfunction "NC_14_27") (pintype "passive+no_connect"))
    )
    (net (code "92") (name "unconnected-(IC72-NC_15-Pad28)") (class "Default")
      (node (ref "IC72") (pin "28") (pinfunction "NC_15_28") (pintype "passive+no_connect"))
    )
    (net (code "93") (name "unconnected-(IC72-NC_16-Pad33)") (class "Default")
      (node (ref "IC72") (pin "33") (pinfunction "NC_16_33") (pintype "passive+no_connect"))
    )
    (net (code "94") (name "unconnected-(IC72-NC_17-Pad35)") (class "Default")
      (node (ref "IC72") (pin "35") (pinfunction "NC_17_35") (pintype "passive+no_connect"))
    )
    (net (code "95") (name "unconnected-(IC72-NC_18-Pad40)") (class "Default")
      (node (ref "IC72") (pin "40") (pinfunction "NC_18_40") (pintype "passive+no_connect"))
    )
    (net (code "96") (name "unconnected-(IC72-NC_19-Pad45)") (class "Default")
      (node (ref "IC72") (pin "45") (pinfunction "NC_19_45") (pintype "passive+no_connect"))
    )
    (net (code "97") (name "unconnected-(IC72-NC_20-Pad46)") (class "Default")
      (node (ref "IC72") (pin "46") (pinfunction "NC_20_46") (pintype "passive+no_connect"))
    )
    (net (code "98") (name "unconnected-(IC72-R{slash}B2#3-Pad6)") (class "Default")
      (node (ref "IC72") (pin "6") (pinfunction "R/B2#3_6") (pintype "passive+no_connect"))
    )
    (net (code "99") (name "unconnected-(R640-Pad1)") (class "Default")
      (node (ref "R640") (pin "1") (pinfunction "1_1") (pintype "passive"))
    )
  )
)
